# TT1-1-Top.net
KiCad netlist of a schematic drawn in Altium Designer
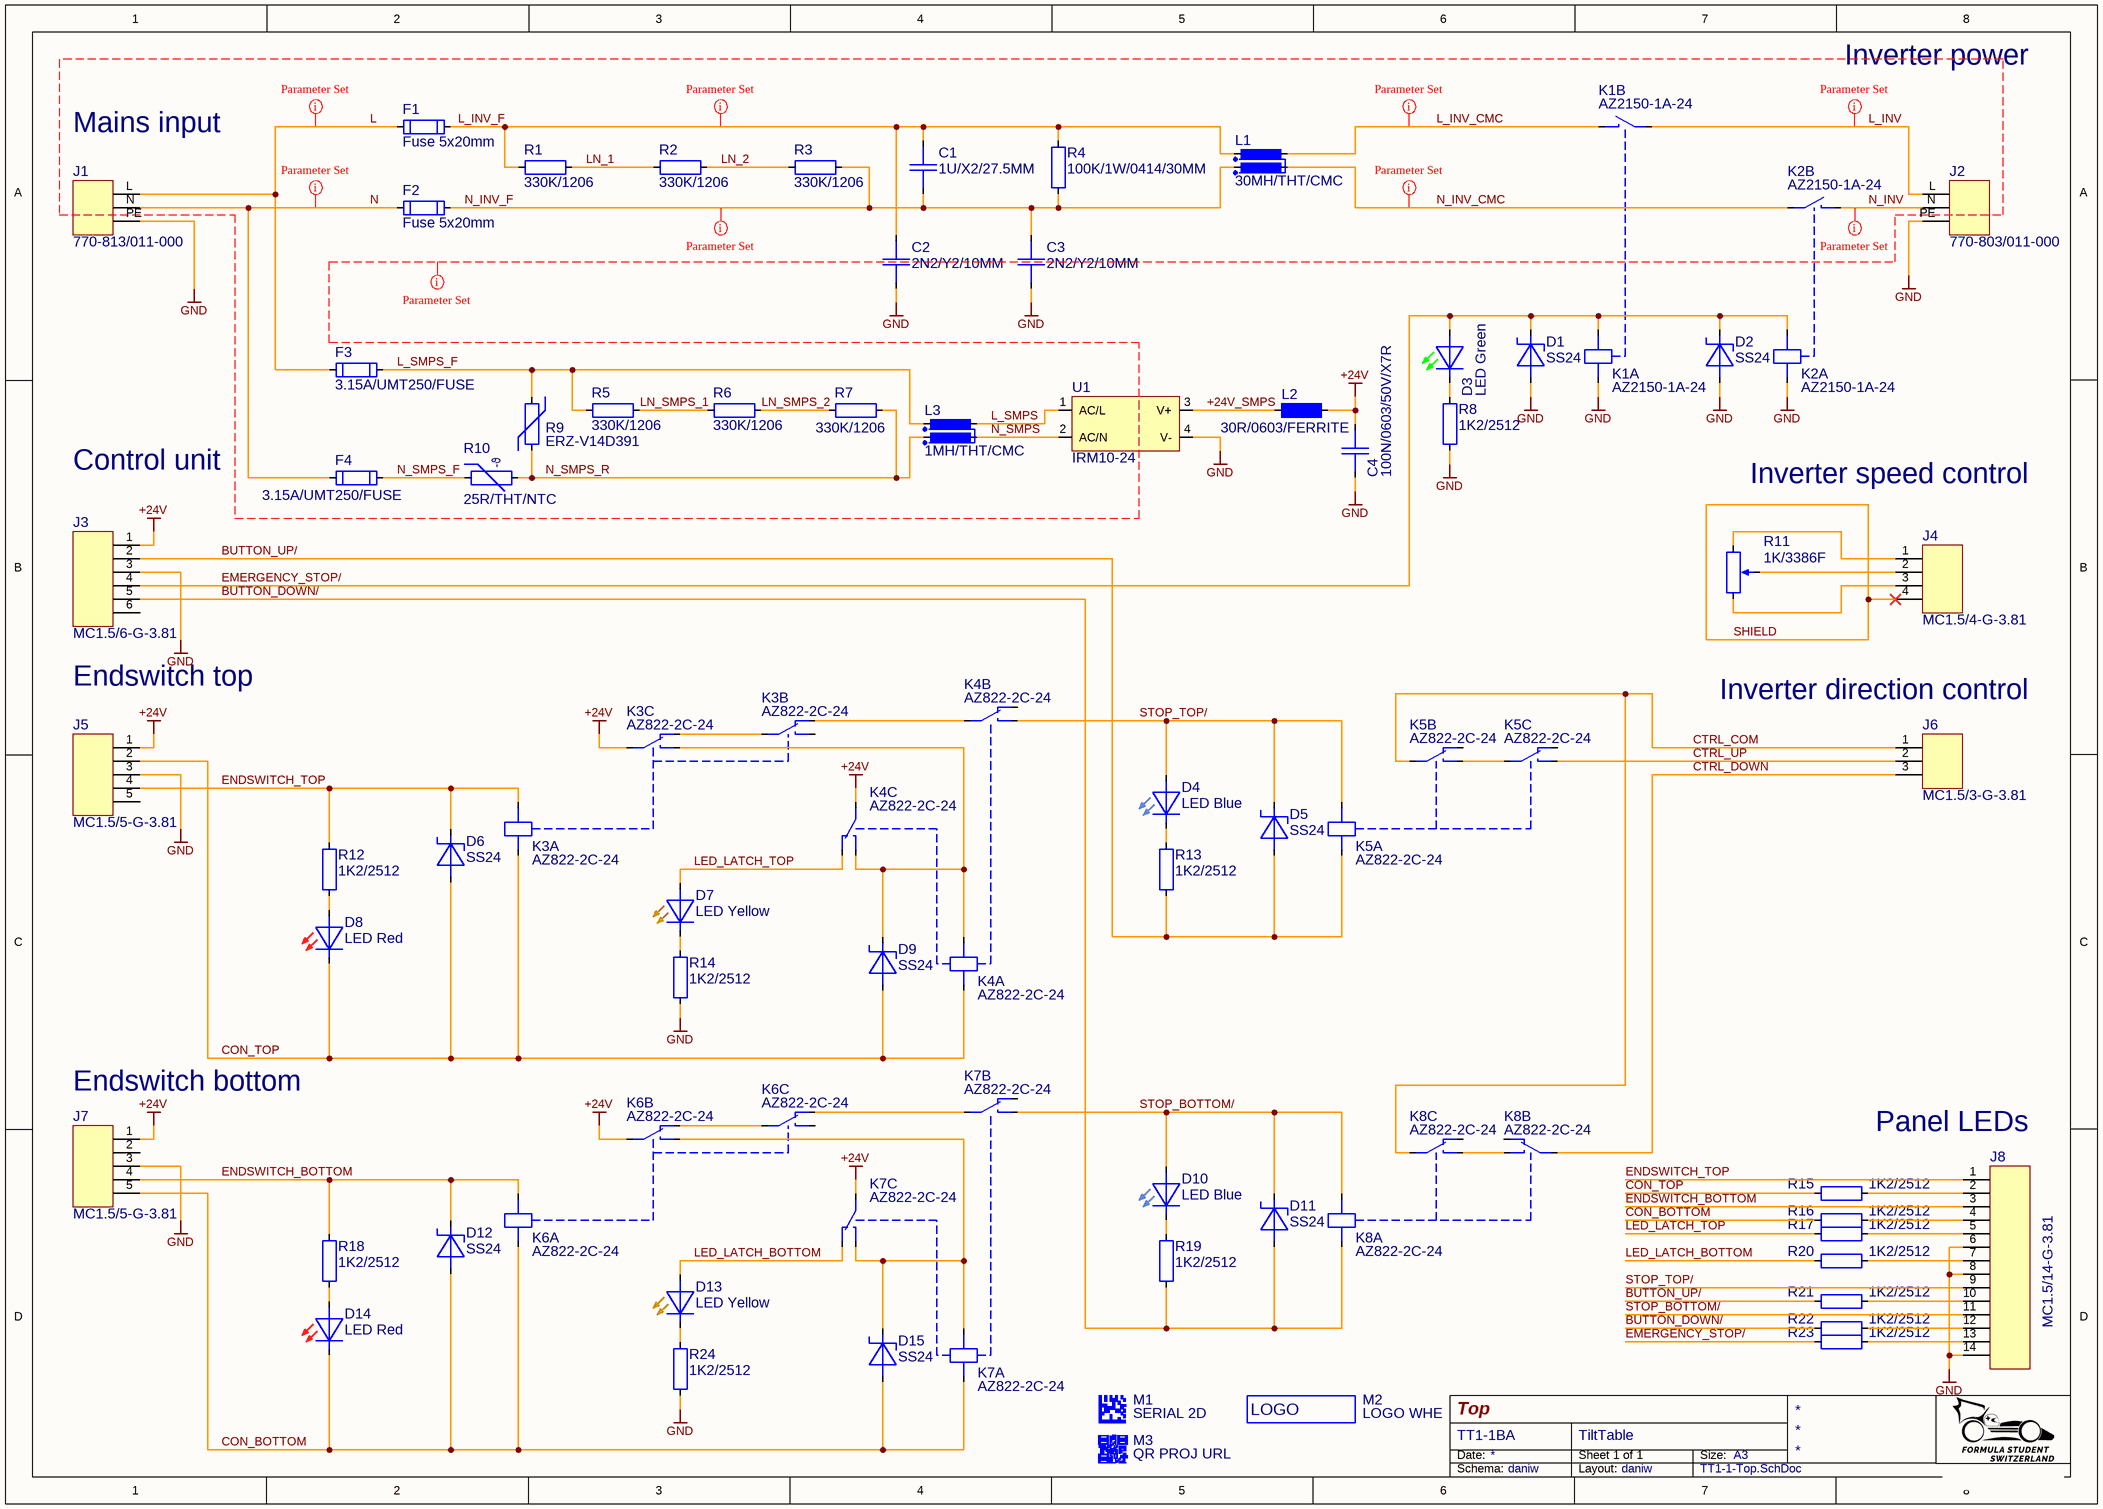
[diagram p0: TT1-1-Top.SchDoc]

(export (version "E")
  (design (tool "Eeschema 10.0.6"))
  (components
    (comp (ref "C1")
      (value "1U/X2/27.5MM")
      (footprint "CAP2750P315X110X190-BL")
      (description "CAP THT 31.5X11X19 1uF 305V X2")
      (fields (field (name "MANUFACTURER") "GENERIC"))
      (libsource (lib "daniw_altium_lib") (part "C"))
    )
    (comp (ref "C2")
      (value "2N2/Y2/10MM")
      (footprint "CAP1000P130X40X90-BL")
      (description "CAP THT 13X4X9 2.2nF 300V Y2")
      (fields (field (name "MANUFACTURER") "GENERIC"))
      (libsource (lib "daniw_altium_lib") (part "C"))
    )
    (comp (ref "C3")
      (value "2N2/Y2/10MM")
      (footprint "CAP1000P130X40X90-BL")
      (description "CAP THT 13X4X9 2.2nF 300V Y2")
      (fields (field (name "MANUFACTURER") "GENERIC"))
      (libsource (lib "daniw_altium_lib") (part "C"))
    )
    (comp (ref "C4")
      (value "100N/0603/50V/X7R")
      (footprint "CAP0603_X7R")
      (description "CAP SM 0603 100nF 50V X7R")
      (fields (field (name "MANUFACTURER") "GENERIC"))
      (libsource (lib "daniw_altium_lib") (part "C"))
    )
    (comp (ref "D1")
      (value "SS24")
      (footprint "DIOM5226X230")
      (description "Si Shottky Diode 2A DO-214AC")
      (fields (field (name "MANUFACTURER") "MSKSEMI"))
      (libsource (lib "daniw_altium_lib") (part "D_Schottky"))
    )
    (comp (ref "D2")
      (value "SS24")
      (footprint "DIOM5226X230")
      (description "Si Shottky Diode 2A DO-214AC")
      (fields (field (name "MANUFACTURER") "MSKSEMI"))
      (libsource (lib "daniw_altium_lib") (part "D_Schottky"))
    )
    (comp (ref "D3")
      (value "LED Green")
      (footprint "LED0603_GREEN")
      (description "Generic LED Green 0603")
      (fields (field (name "PART NUMBER") "LED Green 0603") (field (name "MANUFACTURER") "GENERIC"))
      (libsource (lib "daniw_altium_lib") (part "LED_GREEN"))
    )
    (comp (ref "D4")
      (value "LED Blue")
      (footprint "LED0603_BLUE")
      (description "Generic LED Blue 0603")
      (fields (field (name "PART NUMBER") "LED Blue 0603") (field (name "MANUFACTURER") "GENERIC"))
      (libsource (lib "daniw_altium_lib") (part "LED_BLUE"))
    )
    (comp (ref "D5")
      (value "SS24")
      (footprint "DIOM5226X230")
      (description "Si Shottky Diode 2A DO-214AC")
      (fields (field (name "MANUFACTURER") "MSKSEMI"))
      (libsource (lib "daniw_altium_lib") (part "D_Schottky"))
    )
    (comp (ref "D6")
      (value "SS24")
      (footprint "DIOM5226X230")
      (description "Si Shottky Diode 2A DO-214AC")
      (fields (field (name "MANUFACTURER") "MSKSEMI"))
      (libsource (lib "daniw_altium_lib") (part "D_Schottky"))
    )
    (comp (ref "D7")
      (value "LED Yellow")
      (footprint "LED0603_YELLOW")
      (description "Generic LED Yellow 0603")
      (fields (field (name "PART NUMBER") "LED Yellow 0603") (field (name "MANUFACTURER") "GENERIC"))
      (libsource (lib "daniw_altium_lib") (part "LED_YELLOW"))
    )
    (comp (ref "D8")
      (value "LED Red")
      (footprint "LED0603_RED")
      (description "Generic LED Red 0603")
      (fields (field (name "PART NUMBER") "LED Red 0603") (field (name "MANUFACTURER") "GENERIC"))
      (libsource (lib "daniw_altium_lib") (part "LED_RED"))
    )
    (comp (ref "D9")
      (value "SS24")
      (footprint "DIOM5226X230")
      (description "Si Shottky Diode 2A DO-214AC")
      (fields (field (name "MANUFACTURER") "MSKSEMI"))
      (libsource (lib "daniw_altium_lib") (part "D_Schottky"))
    )
    (comp (ref "D10")
      (value "LED Blue")
      (footprint "LED0603_BLUE")
      (description "Generic LED Blue 0603")
      (fields (field (name "PART NUMBER") "LED Blue 0603") (field (name "MANUFACTURER") "GENERIC"))
      (libsource (lib "daniw_altium_lib") (part "LED_BLUE"))
    )
    (comp (ref "D11")
      (value "SS24")
      (footprint "DIOM5226X230")
      (description "Si Shottky Diode 2A DO-214AC")
      (fields (field (name "MANUFACTURER") "MSKSEMI"))
      (libsource (lib "daniw_altium_lib") (part "D_Schottky"))
    )
    (comp (ref "D12")
      (value "SS24")
      (footprint "DIOM5226X230")
      (description "Si Shottky Diode 2A DO-214AC")
      (fields (field (name "MANUFACTURER") "MSKSEMI"))
      (libsource (lib "daniw_altium_lib") (part "D_Schottky"))
    )
    (comp (ref "D13")
      (value "LED Yellow")
      (footprint "LED0603_YELLOW")
      (description "Generic LED Yellow 0603")
      (fields (field (name "PART NUMBER") "LED Yellow 0603") (field (name "MANUFACTURER") "GENERIC"))
      (libsource (lib "daniw_altium_lib") (part "LED_YELLOW"))
    )
    (comp (ref "D14")
      (value "LED Red")
      (footprint "LED0603_RED")
      (description "Generic LED Red 0603")
      (fields (field (name "PART NUMBER") "LED Red 0603") (field (name "MANUFACTURER") "GENERIC"))
      (libsource (lib "daniw_altium_lib") (part "LED_RED"))
    )
    (comp (ref "D15")
      (value "SS24")
      (footprint "DIOM5226X230")
      (description "Si Shottky Diode 2A DO-214AC")
      (fields (field (name "MANUFACTURER") "MSKSEMI"))
      (libsource (lib "daniw_altium_lib") (part "D_Schottky"))
    )
    (comp (ref "F1")
      (value "Fuse 5x20mm")
      (footprint "OGN_THR")
      (description "open fuse holder, 5 x 20 mm, THR, IEC 60335-1")
      (fields (field (name "PART NUMBER") "Fuse/5x20mm/OGN") (field (name "MANUFACTURER") "Schurter"))
      (libsource (lib "daniw_altium_lib") (part "Fuse"))
    )
    (comp (ref "F2")
      (value "Fuse 5x20mm")
      (footprint "OGN_THR")
      (description "open fuse holder, 5 x 20 mm, THR, IEC 60335-1")
      (fields (field (name "PART NUMBER") "Fuse/5x20mm/OGN") (field (name "MANUFACTURER") "Schurter"))
      (libsource (lib "daniw_altium_lib") (part "Fuse"))
    )
    (comp (ref "F3")
      (value "3.15A/UMT250/FUSE")
      (footprint "UMT250")
      (description "Fuse 250VAC 3.15A UMT250")
      (fields (field (name "MANUFACTURER") "Schurter"))
      (libsource (lib "daniw_altium_lib") (part "Fuse"))
    )
    (comp (ref "F4")
      (value "3.15A/UMT250/FUSE")
      (footprint "UMT250")
      (description "Fuse 250VAC 3.15A UMT250")
      (fields (field (name "MANUFACTURER") "Schurter"))
      (libsource (lib "daniw_altium_lib") (part "Fuse"))
    )
    (comp (ref "J1")
      (value "770-813/011-000")
      (footprint "770-813/011-000")
      (description "Wago 770-813/011-000")
      (fields (field (name "MANUFACTURER") "Wago"))
      (libsource (lib "") (part "CON3_MAINS_1"))
    )
    (comp (ref "J2")
      (value "770-803/011-000")
      (footprint "770-803/011-000")
      (description "Wago 770-803/011-000")
      (fields (field (name "MANUFACTURER") "Wago"))
      (libsource (lib "daniw_altium_lib") (part "CON3_MAINS"))
    )
    (comp (ref "J3")
      (value "MC1.5/6-G-3.81")
      (footprint "MC1.5/6-G-3.81")
      (description "Phoenix contact MC 1,5/ 6-G-3,81")
      (fields (field (name "MANUFACTURER") "Phoenix"))
      (libsource (lib "daniw_altium_lib") (part "CON6"))
    )
    (comp (ref "J4")
      (value "MC1.5/4-G-3.81")
      (footprint "MC1.5/4-G-3.81")
      (description "Phoenix contact MC 1,5/ 4-G-3,81")
      (fields (field (name "MANUFACTURER") "Phoenix"))
      (libsource (lib "daniw_altium_lib") (part "CON4"))
    )
    (comp (ref "J5")
      (value "MC1.5/5-G-3.81")
      (footprint "MC1.5/5-G-3.81")
      (description "Phoenix contact MC 1,5/ 5-G-3,81")
      (fields (field (name "MANUFACTURER") "Phoenix"))
      (libsource (lib "daniw_altium_lib") (part "CON5"))
    )
    (comp (ref "J6")
      (value "MC1.5/3-G-3.81")
      (footprint "MC1.5/3-G-3.81")
      (description "Phoenix contact MC 1,5/ 3-G-3,81")
      (fields (field (name "MANUFACTURER") "Phoenix"))
      (libsource (lib "daniw_altium_lib") (part "CON3"))
    )
    (comp (ref "J7")
      (value "MC1.5/5-G-3.81")
      (footprint "MC1.5/5-G-3.81")
      (description "Phoenix contact MC 1,5/ 5-G-3,81")
      (fields (field (name "MANUFACTURER") "Phoenix"))
      (libsource (lib "daniw_altium_lib") (part "CON5"))
    )
    (comp (ref "J8")
      (value "MC1.5/14-G-3.81")
      (footprint "MC1.5/14-G-3.81")
      (description "Phoenix contact MC 1,5/ 14-G-3,81")
      (fields (field (name "MANUFACTURER") "Phoenix"))
      (libsource (lib "daniw_altium_lib") (part "CON14"))
    )
    (comp (ref "K1")
      (value "AZ2150-1A-24")
      (footprint "AZ2150-SPST-NO")
      (description "Miniature Power Relay, SPST-NO, 24V Coil, 40A 30VDC 300VAC")
      (fields (field (name "MANUFACTURER") "Zettler"))
      (libsource (lib "daniw_altium_lib") (part "REL_SPST_NO"))
    )
    (comp (ref "K2")
      (value "AZ2150-1A-24")
      (footprint "AZ2150-SPST-NO")
      (description "Miniature Power Relay, SPST-NO, 24V Coil, 40A 30VDC 300VAC")
      (fields (field (name "MANUFACTURER") "Zettler"))
      (libsource (lib "daniw_altium_lib") (part "REL_SPST_NO"))
    )
    (comp (ref "K3")
      (value "AZ822-2C-24")
      (footprint "AZ822")
      (description "Subminiature DIP Relay, DPDT, 24V 98mW Coil, 2A 220VDC 250VAC")
      (fields (field (name "MANUFACTURER") "Zettler"))
      (libsource (lib "daniw_altium_lib") (part "REL_DPDT"))
    )
    (comp (ref "K4")
      (value "AZ822-2C-24")
      (footprint "AZ822")
      (description "Subminiature DIP Relay, DPDT, 24V 98mW Coil, 2A 220VDC 250VAC")
      (fields (field (name "MANUFACTURER") "Zettler"))
      (libsource (lib "daniw_altium_lib") (part "REL_DPDT"))
    )
    (comp (ref "K5")
      (value "AZ822-2C-24")
      (footprint "AZ822")
      (description "Subminiature DIP Relay, DPDT, 24V 98mW Coil, 2A 220VDC 250VAC")
      (fields (field (name "MANUFACTURER") "Zettler"))
      (libsource (lib "daniw_altium_lib") (part "REL_DPDT"))
    )
    (comp (ref "K6")
      (value "AZ822-2C-24")
      (footprint "AZ822")
      (description "Subminiature DIP Relay, DPDT, 24V 98mW Coil, 2A 220VDC 250VAC")
      (fields (field (name "MANUFACTURER") "Zettler"))
      (libsource (lib "daniw_altium_lib") (part "REL_DPDT"))
    )
    (comp (ref "K7")
      (value "AZ822-2C-24")
      (footprint "AZ822")
      (description "Subminiature DIP Relay, DPDT, 24V 98mW Coil, 2A 220VDC 250VAC")
      (fields (field (name "MANUFACTURER") "Zettler"))
      (libsource (lib "daniw_altium_lib") (part "REL_DPDT"))
    )
    (comp (ref "K8")
      (value "AZ822-2C-24")
      (footprint "AZ822")
      (description "Subminiature DIP Relay, DPDT, 24V 98mW Coil, 2A 220VDC 250VAC")
      (fields (field (name "MANUFACTURER") "Zettler"))
      (libsource (lib "daniw_altium_lib") (part "REL_DPDT"))
    )
    (comp (ref "L1")
      (value "30MH/THT/CMC")
      (footprint "CMC-WE-CMBNC-XL-7448050530")
      (description "CMC 30mH 5A Würth CMBNC 7448050530")
      (fields (field (name "MANUFACTURER") "Würth"))
      (libsource (lib "daniw_altium_lib") (part "L_CMC_2"))
    )
    (comp (ref "L2")
      (value "30R/0603/FERRITE")
      (footprint "FB0603")
      (description "30R@100MHz 5A 0603 Ferrite")
      (fields (field (name "MANUFACTURER") "GENERIC"))
      (libsource (lib "daniw_altium_lib") (part "Ferrite"))
    )
    (comp (ref "L3")
      (value "1MH/THT/CMC")
      (footprint "DFKH-CASE-50-2")
      (description "CMC 1mH 2A THT Schurter DFKH-14-0003")
      (fields (field (name "MANUFACTURER") "SCHURTER"))
      (libsource (lib "daniw_altium_lib") (part "L_CMC_2"))
    )
    (comp (ref "M1")
      (value "SERIAL 2D")
      (footprint "SERIAL-2D-10MM")
      (description "2D Serial number placeholder, Dotmatrix or QR, size: 10mm")
      (fields (field (name "PART NUMBER") "SERIAL 2D 10MM") (field (name "MANUFACTURER") "NONE"))
      (libsource (lib "daniw_altium_lib") (part "SERIAL-2D"))
    )
    (comp (ref "M2")
      (value "LOGO WHE")
      (footprint "LOGO-WHE-10MM")
      (description "WHE logo, size 10mm")
      (fields (field (name "PART NUMBER") "LOGO WHE 10MM") (field (name "MANUFACTURER") "NONE"))
      (libsource (lib "daniw_altium_lib") (part "LOGO"))
    )
    (comp (ref "M3")
      (value "QR PROJ URL")
      (footprint "QR-PROJECT-URL-10MM")
      (description "QR Code, Project URL, 10mm")
      (fields (field (name "PART NUMBER") "QR PROJ URL 10MM") (field (name "MANUFACTURER") "NONE"))
      (libsource (lib "daniw_altium_lib") (part "QR-PROJ-URL"))
    )
    (comp (ref "R1")
      (value "330K/1206")
      (footprint "R1206-0.80-WW")
      (description "RES SM 1206 330K")
      (fields (field (name "MANUFACTURER") "GENERIC"))
      (libsource (lib "daniw_altium_lib") (part "R"))
    )
    (comp (ref "R2")
      (value "330K/1206")
      (footprint "R1206-0.80-WW")
      (description "RES SM 1206 330K")
      (fields (field (name "MANUFACTURER") "GENERIC"))
      (libsource (lib "daniw_altium_lib") (part "R"))
    )
    (comp (ref "R3")
      (value "330K/1206")
      (footprint "R1206-0.80-WW")
      (description "RES SM 1206 330K")
      (fields (field (name "MANUFACTURER") "GENERIC"))
      (libsource (lib "daniw_altium_lib") (part "R"))
    )
    (comp (ref "R4")
      (value "100K/1W/0414/30MM")
      (footprint "RESAD3000W80L1200D400B")
      (description "RES TH 1W 0414 30MM 100K")
      (fields (field (name "MANUFACTURER") "GENERIC"))
      (libsource (lib "daniw_altium_lib") (part "R"))
    )
    (comp (ref "R5")
      (value "330K/1206")
      (footprint "R1206-0.80-WW")
      (description "RES SM 1206 330K")
      (fields (field (name "MANUFACTURER") "GENERIC"))
      (libsource (lib "daniw_altium_lib") (part "R"))
    )
    (comp (ref "R6")
      (value "330K/1206")
      (footprint "R1206-0.80-WW")
      (description "RES SM 1206 330K")
      (fields (field (name "MANUFACTURER") "GENERIC"))
      (libsource (lib "daniw_altium_lib") (part "R"))
    )
    (comp (ref "R7")
      (value "330K/1206")
      (footprint "R1206-0.80-WW")
      (description "RES SM 1206 330K")
      (fields (field (name "MANUFACTURER") "GENERIC"))
      (libsource (lib "daniw_altium_lib") (part "R"))
    )
    (comp (ref "R8")
      (value "1K2/2512")
      (footprint "R2512-0.65-WW")
      (description "RES SM 2512 1K2")
      (fields (field (name "MANUFACTURER") "GENERIC"))
      (libsource (lib "daniw_altium_lib") (part "R"))
    )
    (comp (ref "R9")
      (value "ERZ-V14D391")
      (footprint "RESD750W80D155")
      (description "VARISTOR 391V 6kA")
      (fields (field (name "MANUFACTURER") "GENERIC"))
      (libsource (lib "daniw_altium_lib") (part "R_VAR"))
    )
    (comp (ref "R10")
      (value "25R/THT/NTC")
      (footprint "RESD500W60D115")
      (description "RES NTC THT 5 25R")
      (fields (field (name "MANUFACTURER") "GENERIC"))
      (libsource (lib "daniw_altium_lib") (part "R_NTC"))
    )
    (comp (ref "R11")
      (value "1K/3386F")
      (footprint "3386F")
      (description "RES POT 3386F 1K")
      (fields (field (name "MANUFACTURER") "Bourns"))
      (libsource (lib "daniw_altium_lib") (part "R_POT"))
    )
    (comp (ref "R12")
      (value "1K2/2512")
      (footprint "R2512-0.65-WW")
      (description "RES SM 2512 1K2")
      (fields (field (name "MANUFACTURER") "GENERIC"))
      (libsource (lib "daniw_altium_lib") (part "R"))
    )
    (comp (ref "R13")
      (value "1K2/2512")
      (footprint "R2512-0.65-WW")
      (description "RES SM 2512 1K2")
      (fields (field (name "MANUFACTURER") "GENERIC"))
      (libsource (lib "daniw_altium_lib") (part "R"))
    )
    (comp (ref "R14")
      (value "1K2/2512")
      (footprint "R2512-0.65-WW")
      (description "RES SM 2512 1K2")
      (fields (field (name "MANUFACTURER") "GENERIC"))
      (libsource (lib "daniw_altium_lib") (part "R"))
    )
    (comp (ref "R15")
      (value "1K2/2512")
      (footprint "R2512-0.65-WW")
      (description "RES SM 2512 1K2")
      (fields (field (name "MANUFACTURER") "GENERIC"))
      (libsource (lib "daniw_altium_lib") (part "R"))
    )
    (comp (ref "R16")
      (value "1K2/2512")
      (footprint "R2512-0.65-WW")
      (description "RES SM 2512 1K2")
      (fields (field (name "MANUFACTURER") "GENERIC"))
      (libsource (lib "daniw_altium_lib") (part "R"))
    )
    (comp (ref "R17")
      (value "1K2/2512")
      (footprint "R2512-0.65-WW")
      (description "RES SM 2512 1K2")
      (fields (field (name "MANUFACTURER") "GENERIC"))
      (libsource (lib "daniw_altium_lib") (part "R"))
    )
    (comp (ref "R18")
      (value "1K2/2512")
      (footprint "R2512-0.65-WW")
      (description "RES SM 2512 1K2")
      (fields (field (name "MANUFACTURER") "GENERIC"))
      (libsource (lib "daniw_altium_lib") (part "R"))
    )
    (comp (ref "R19")
      (value "1K2/2512")
      (footprint "R2512-0.65-WW")
      (description "RES SM 2512 1K2")
      (fields (field (name "MANUFACTURER") "GENERIC"))
      (libsource (lib "daniw_altium_lib") (part "R"))
    )
    (comp (ref "R20")
      (value "1K2/2512")
      (footprint "R2512-0.65-WW")
      (description "RES SM 2512 1K2")
      (fields (field (name "MANUFACTURER") "GENERIC"))
      (libsource (lib "daniw_altium_lib") (part "R"))
    )
    (comp (ref "R21")
      (value "1K2/2512")
      (footprint "R2512-0.65-WW")
      (description "RES SM 2512 1K2")
      (fields (field (name "MANUFACTURER") "GENERIC"))
      (libsource (lib "daniw_altium_lib") (part "R"))
    )
    (comp (ref "R22")
      (value "1K2/2512")
      (footprint "R2512-0.65-WW")
      (description "RES SM 2512 1K2")
      (fields (field (name "MANUFACTURER") "GENERIC"))
      (libsource (lib "daniw_altium_lib") (part "R"))
    )
    (comp (ref "R23")
      (value "1K2/2512")
      (footprint "R2512-0.65-WW")
      (description "RES SM 2512 1K2")
      (fields (field (name "MANUFACTURER") "GENERIC"))
      (libsource (lib "daniw_altium_lib") (part "R"))
    )
    (comp (ref "R24")
      (value "1K2/2512")
      (footprint "R2512-0.65-WW")
      (description "RES SM 2512 1K2")
      (fields (field (name "MANUFACTURER") "GENERIC"))
      (libsource (lib "daniw_altium_lib") (part "R"))
    )
    (comp (ref "U1")
      (value "IRM10-24")
      (footprint "IRM10")
      (description "10W AC-DC PCB-Mount Green Power Module, 24V")
      (libsource (lib "daniw_altium_lib") (part "IRM30"))
    )
  )
  (nets
    (net (code "1") (name "+24V") (class "Default")
      (node (ref "C4") (pin "1") (pinfunction "1_1") (pintype "passive"))
      (node (ref "J3") (pin "1") (pintype "passive"))
      (node (ref "J5") (pin "1") (pintype "passive"))
      (node (ref "J7") (pin "1") (pintype "passive"))
      (node (ref "K3") (pin "6") (pinfunction "COM2_6") (pintype "passive"))
      (node (ref "K4") (pin "6") (pinfunction "COM2_6") (pintype "passive"))
      (node (ref "K6") (pin "3") (pinfunction "COM1_3") (pintype "passive"))
      (node (ref "K7") (pin "6") (pinfunction "COM2_6") (pintype "passive"))
      (node (ref "L2") (pin "2") (pinfunction "2_2") (pintype "passive"))
    )
    (net (code "2") (name "/+24V_SMPS") (class "Default")
      (node (ref "L2") (pin "1") (pinfunction "1_1") (pintype "passive"))
      (node (ref "U1") (pin "3") (pinfunction "V+_3") (pintype "passive"))
    )
    (net (code "3") (name "/BUTTON_DOWN{slash}") (class "Default")
      (node (ref "D11") (pin "2") (pinfunction "2_2") (pintype "passive"))
      (node (ref "J3") (pin "5") (pintype "passive"))
      (node (ref "K8") (pin "2") (pinfunction "2_2") (pintype "passive"))
      (node (ref "R19") (pin "2") (pinfunction "2_2") (pintype "passive"))
      (node (ref "R22") (pin "1") (pinfunction "1_1") (pintype "passive"))
    )
    (net (code "4") (name "/BUTTON_UP{slash}") (class "Default")
      (node (ref "D5") (pin "2") (pinfunction "2_2") (pintype "passive"))
      (node (ref "J3") (pin "2") (pintype "passive"))
      (node (ref "K5") (pin "1") (pinfunction "1_1") (pintype "passive"))
      (node (ref "R13") (pin "2") (pinfunction "2_2") (pintype "passive"))
      (node (ref "R21") (pin "1") (pinfunction "1_1") (pintype "passive"))
    )
    (net (code "5") (name "/CON_BOTTOM") (class "Default")
      (node (ref "D12") (pin "2") (pinfunction "2_2") (pintype "passive"))
      (node (ref "D14") (pin "1") (pinfunction "1_1") (pintype "passive"))
      (node (ref "D15") (pin "2") (pinfunction "2_2") (pintype "passive"))
      (node (ref "J7") (pin "5") (pintype "passive"))
      (node (ref "K6") (pin "2") (pinfunction "2_2") (pintype "passive"))
      (node (ref "K7") (pin "2") (pinfunction "2_2") (pintype "passive"))
      (node (ref "R16") (pin "1") (pinfunction "1_1") (pintype "passive"))
    )
    (net (code "6") (name "/CON_TOP") (class "Default")
      (node (ref "D6") (pin "2") (pinfunction "2_2") (pintype "passive"))
      (node (ref "D8") (pin "1") (pinfunction "1_1") (pintype "passive"))
      (node (ref "D9") (pin "2") (pinfunction "2_2") (pintype "passive"))
      (node (ref "J5") (pin "2") (pintype "passive"))
      (node (ref "K3") (pin "2") (pinfunction "2_2") (pintype "passive"))
      (node (ref "K4") (pin "2") (pinfunction "2_2") (pintype "passive"))
      (node (ref "R15") (pin "1") (pinfunction "1_1") (pintype "passive"))
    )
    (net (code "7") (name "/CTRL_COM") (class "Default")
      (node (ref "J6") (pin "1") (pintype "passive"))
      (node (ref "K5") (pin "3") (pinfunction "COM1_3") (pintype "passive"))
      (node (ref "K8") (pin "6") (pinfunction "COM2_6") (pintype "passive"))
    )
    (net (code "8") (name "/CTRL_DOWN") (class "Default")
      (node (ref "J6") (pin "3") (pintype "passive"))
      (node (ref "K8") (pin "3") (pinfunction "COM1_3") (pintype "passive"))
    )
    (net (code "9") (name "/CTRL_UP") (class "Default")
      (node (ref "J6") (pin "2") (pintype "passive"))
      (node (ref "K5") (pin "8") (pinfunction "NO2_8") (pintype "passive"))
    )
    (net (code "10") (name "/EMERGENCY_STOP{slash}") (class "Default")
      (node (ref "D1") (pin "1") (pinfunction "1_1") (pintype "passive"))
      (node (ref "D2") (pin "1") (pinfunction "1_1") (pintype "passive"))
      (node (ref "D3") (pin "2") (pinfunction "2_2") (pintype "passive"))
      (node (ref "J3") (pin "4") (pintype "passive"))
      (node (ref "K1") (pin "1") (pinfunction "1_1") (pintype "passive"))
      (node (ref "K2") (pin "1") (pinfunction "1_1") (pintype "passive"))
      (node (ref "R23") (pin "1") (pinfunction "1_1") (pintype "passive"))
    )
    (net (code "11") (name "/ENDSWITCH_BOTTOM") (class "Default")
      (node (ref "D12") (pin "1") (pinfunction "1_1") (pintype "passive"))
      (node (ref "J7") (pin "4") (pintype "passive"))
      (node (ref "J8") (pin "3") (pintype "passive"))
      (node (ref "K6") (pin "1") (pinfunction "1_1") (pintype "passive"))
      (node (ref "R18") (pin "1") (pinfunction "1_1") (pintype "passive"))
    )
    (net (code "12") (name "/ENDSWITCH_TOP") (class "Default")
      (node (ref "D6") (pin "1") (pinfunction "1_1") (pintype "passive"))
      (node (ref "J5") (pin "4") (pintype "passive"))
      (node (ref "J8") (pin "1") (pintype "passive"))
      (node (ref "K3") (pin "1") (pinfunction "1_1") (pintype "passive"))
      (node (ref "R12") (pin "1") (pinfunction "1_1") (pintype "passive"))
    )
    (net (code "13") (name "/L") (class "Default")
      (node (ref "F1") (pin "1") (pinfunction "1_1") (pintype "passive"))
      (node (ref "F3") (pin "1") (pinfunction "1_1") (pintype "passive"))
      (node (ref "J1") (pin "L") (pintype "passive"))
    )
    (net (code "14") (name "/LED_LATCH_BOTTOM") (class "Default")
      (node (ref "D13") (pin "2") (pinfunction "2_2") (pintype "passive"))
      (node (ref "K7") (pin "7") (pinfunction "NC2_7") (pintype "passive"))
      (node (ref "R20") (pin "1") (pinfunction "1_1") (pintype "passive"))
    )
    (net (code "15") (name "/LED_LATCH_TOP") (class "Default")
      (node (ref "D7") (pin "2") (pinfunction "2_2") (pintype "passive"))
      (node (ref "K4") (pin "7") (pinfunction "NC2_7") (pintype "passive"))
      (node (ref "R17") (pin "1") (pinfunction "1_1") (pintype "passive"))
    )
    (net (code "16") (name "/LN_1") (class "Default")
      (node (ref "R1") (pin "2") (pinfunction "2_2") (pintype "passive"))
      (node (ref "R2") (pin "1") (pinfunction "1_1") (pintype "passive"))
    )
    (net (code "17") (name "/LN_2") (class "Default")
      (node (ref "R2") (pin "2") (pinfunction "2_2") (pintype "passive"))
      (node (ref "R3") (pin "1") (pinfunction "1_1") (pintype "passive"))
    )
    (net (code "18") (name "/LN_SMPS_1") (class "Default")
      (node (ref "R5") (pin "2") (pinfunction "2_2") (pintype "passive"))
      (node (ref "R6") (pin "2") (pinfunction "2_2") (pintype "passive"))
    )
    (net (code "19") (name "/LN_SMPS_2") (class "Default")
      (node (ref "R6") (pin "1") (pinfunction "1_1") (pintype "passive"))
      (node (ref "R7") (pin "1") (pinfunction "1_1") (pintype "passive"))
    )
    (net (code "20") (name "/L_INV") (class "Default")
      (node (ref "J2") (pin "L") (pintype "passive"))
      (node (ref "K1") (pin "3") (pinfunction "COM1_3") (pintype "passive"))
    )
    (net (code "21") (name "/L_INV_CMC") (class "Default")
      (node (ref "K1") (pin "4") (pinfunction "NO1_4") (pintype "passive"))
      (node (ref "L1") (pin "3") (pinfunction "3_3") (pintype "passive"))
    )
    (net (code "22") (name "/L_INV_F") (class "Default")
      (node (ref "C1") (pin "1") (pinfunction "1_1") (pintype "passive"))
      (node (ref "C2") (pin "1") (pinfunction "1_1") (pintype "passive"))
      (node (ref "F1") (pin "2") (pinfunction "2_2") (pintype "passive"))
      (node (ref "L1") (pin "1") (pinfunction "1_1") (pintype "passive"))
      (node (ref "R1") (pin "1") (pinfunction "1_1") (pintype "passive"))
      (node (ref "R4") (pin "1") (pinfunction "1_1") (pintype "passive"))
    )
    (net (code "23") (name "/L_SMPS") (class "Default")
      (node (ref "L3") (pin "3") (pinfunction "3_3") (pintype "passive"))
      (node (ref "U1") (pin "1") (pinfunction "AC/L_1") (pintype "passive"))
    )
    (net (code "24") (name "/L_SMPS_F") (class "Default")
      (node (ref "F3") (pin "2") (pinfunction "2_2") (pintype "passive"))
      (node (ref "L3") (pin "1") (pinfunction "1_1") (pintype "passive"))
      (node (ref "R5") (pin "1") (pinfunction "1_1") (pintype "passive"))
      (node (ref "R9") (pin "1") (pinfunction "1_1") (pintype "passive"))
    )
    (net (code "25") (name "/N") (class "Default")
      (node (ref "F2") (pin "1") (pinfunction "1_1") (pintype "passive"))
      (node (ref "F4") (pin "1") (pinfunction "1_1") (pintype "passive"))
      (node (ref "J1") (pin "N") (pintype "passive"))
    )
    (net (code "26") (name "/N_INV") (class "Default")
      (node (ref "J2") (pin "N") (pintype "passive"))
      (node (ref "K2") (pin "4") (pinfunction "NO1_4") (pintype "passive"))
    )
    (net (code "27") (name "/N_INV_CMC") (class "Default")
      (node (ref "K2") (pin "3") (pinfunction "COM1_3") (pintype "passive"))
      (node (ref "L1") (pin "4") (pinfunction "4_4") (pintype "passive"))
    )
    (net (code "28") (name "/N_INV_F") (class "Default")
      (node (ref "C1") (pin "2") (pinfunction "2_2") (pintype "passive"))
      (node (ref "C3") (pin "1") (pinfunction "1_1") (pintype "passive"))
      (node (ref "F2") (pin "2") (pinfunction "2_2") (pintype "passive"))
      (node (ref "L1") (pin "2") (pinfunction "2_2") (pintype "passive"))
      (node (ref "R3") (pin "2") (pinfunction "2_2") (pintype "passive"))
      (node (ref "R4") (pin "2") (pinfunction "2_2") (pintype "passive"))
    )
    (net (code "29") (name "/N_SMPS") (class "Default")
      (node (ref "L3") (pin "4") (pinfunction "4_4") (pintype "passive"))
      (node (ref "U1") (pin "2") (pinfunction "AC/N_2") (pintype "passive"))
    )
    (net (code "30") (name "/N_SMPS_F") (class "Default")
      (node (ref "F4") (pin "2") (pinfunction "2_2") (pintype "passive"))
      (node (ref "R10") (pin "1") (pinfunction "1_1") (pintype "passive"))
    )
    (net (code "31") (name "/N_SMPS_R") (class "Default")
      (node (ref "L3") (pin "2") (pinfunction "2_2") (pintype "passive"))
      (node (ref "R10") (pin "2") (pinfunction "2_2") (pintype "passive"))
      (node (ref "R7") (pin "2") (pinfunction "2_2") (pintype "passive"))
      (node (ref "R9") (pin "2") (pinfunction "2_2") (pintype "passive"))
    )
    (net (code "32") (name "/SHIELD") (class "Default")
      (node (ref "J4") (pin "4") (pintype "passive+no_connect"))
    )
    (net (code "33") (name "/STOP_BOTTOM{slash}") (class "Default")
      (node (ref "D10") (pin "2") (pinfunction "2_2") (pintype "passive"))
      (node (ref "D11") (pin "1") (pinfunction "1_1") (pintype "passive"))
      (node (ref "J8") (pin "11") (pintype "passive"))
      (node (ref "K7") (pin "5") (pinfunction "NO1_5") (pintype "passive"))
      (node (ref "K8") (pin "1") (pinfunction "1_1") (pintype "passive"))
    )
    (net (code "34") (name "/STOP_TOP{slash}") (class "Default")
      (node (ref "D4") (pin "2") (pinfunction "2_2") (pintype "passive"))
      (node (ref "D5") (pin "1") (pinfunction "1_1") (pintype "passive"))
      (node (ref "J8") (pin "9") (pintype "passive"))
      (node (ref "K4") (pin "5") (pinfunction "NO1_5") (pintype "passive"))
      (node (ref "K5") (pin "2") (pinfunction "2_2") (pintype "passive"))
    )
    (net (code "35") (name "GND") (class "Default")
      (node (ref "C2") (pin "2") (pinfunction "2_2") (pintype "passive"))
      (node (ref "C3") (pin "2") (pinfunction "2_2") (pintype "passive"))
      (node (ref "C4") (pin "2") (pinfunction "2_2") (pintype "passive"))
      (node (ref "D1") (pin "2") (pinfunction "2_2") (pintype "passive"))
      (node (ref "D2") (pin "2") (pinfunction "2_2") (pintype "passive"))
      (node (ref "J1") (pin "PE") (pintype "passive"))
      (node (ref "J2") (pin "PE") (pintype "passive"))
      (node (ref "J3") (pin "3") (pintype "passive"))
      (node (ref "J5") (pin "3") (pintype "passive"))
      (node (ref "J7") (pin "3") (pintype "passive"))
      (node (ref "J8") (pin "14") (pintype "passive"))
      (node (ref "J8") (pin "6") (pintype "passive"))
      (node (ref "J8") (pin "8") (pintype "passive"))
      (node (ref "K1") (pin "2") (pinfunction "2_2") (pintype "passive"))
      (node (ref "K2") (pin "2") (pinfunction "2_2") (pintype "passive"))
      (node (ref "R14") (pin "2") (pinfunction "2_2") (pintype "passive"))
      (node (ref "R24") (pin "2") (pinfunction "2_2") (pintype "passive"))
      (node (ref "R8") (pin "2") (pinfunction "2_2") (pintype "passive"))
      (node (ref "U1") (pin "4") (pinfunction "V-_4") (pintype "passive"))
    )
    (net (code "36") (name "Net-(D3-Pad1)") (class "Default")
      (node (ref "D3") (pin "1") (pinfunction "1_1") (pintype "passive"))
      (node (ref "R8") (pin "1") (pinfunction "1_1") (pintype "passive"))
    )
    (net (code "37") (name "Net-(D4-Pad1)") (class "Default")
      (node (ref "D4") (pin "1") (pinfunction "1_1") (pintype "passive"))
      (node (ref "R13") (pin "1") (pinfunction "1_1") (pintype "passive"))
    )
    (net (code "38") (name "Net-(D7-Pad1)") (class "Default")
      (node (ref "D7") (pin "1") (pinfunction "1_1") (pintype "passive"))
      (node (ref "R14") (pin "1") (pinfunction "1_1") (pintype "passive"))
    )
    (net (code "39") (name "Net-(D8-Pad2)") (class "Default")
      (node (ref "D8") (pin "2") (pinfunction "2_2") (pintype "passive"))
      (node (ref "R12") (pin "2") (pinfunction "2_2") (pintype "passive"))
    )
    (net (code "40") (name "Net-(D10-Pad1)") (class "Default")
      (node (ref "D10") (pin "1") (pinfunction "1_1") (pintype "passive"))
      (node (ref "R19") (pin "1") (pinfunction "1_1") (pintype "passive"))
    )
    (net (code "41") (name "Net-(D13-Pad1)") (class "Default")
      (node (ref "D13") (pin "1") (pinfunction "1_1") (pintype "passive"))
      (node (ref "R24") (pin "1") (pinfunction "1_1") (pintype "passive"))
    )
    (net (code "42") (name "Net-(D14-Pad2)") (class "Default")
      (node (ref "D14") (pin "2") (pinfunction "2_2") (pintype "passive"))
      (node (ref "R18") (pin "2") (pinfunction "2_2") (pintype "passive"))
    )
    (net (code "43") (name "Net-(J4-Pad1)") (class "Default")
      (node (ref "J4") (pin "1") (pintype "passive"))
      (node (ref "R11") (pin "2") (pinfunction "2_2") (pintype "passive"))
    )
    (net (code "44") (name "Net-(J4-Pad2)") (class "Default")
      (node (ref "J4") (pin "2") (pintype "passive"))
      (node (ref "R11") (pin "3") (pinfunction "3_3") (pintype "passive"))
    )
    (net (code "45") (name "Net-(J4-Pad3)") (class "Default")
      (node (ref "J4") (pin "3") (pintype "passive"))
      (node (ref "R11") (pin "1") (pinfunction "1_1") (pintype "passive"))
    )
    (net (code "46") (name "Net-(J8-Pad2)") (class "Default")
      (node (ref "J8") (pin "2") (pintype "passive"))
      (node (ref "R15") (pin "2") (pinfunction "2_2") (pintype "passive"))
    )
    (net (code "47") (name "Net-(J8-Pad4)") (class "Default")
      (node (ref "J8") (pin "4") (pintype "passive"))
      (node (ref "R16") (pin "2") (pinfunction "2_2") (pintype "passive"))
    )
    (net (code "48") (name "Net-(J8-Pad5)") (class "Default")
      (node (ref "J8") (pin "5") (pintype "passive"))
      (node (ref "R17") (pin "2") (pinfunction "2_2") (pintype "passive"))
    )
    (net (code "49") (name "Net-(J8-Pad7)") (class "Default")
      (node (ref "J8") (pin "7") (pintype "passive"))
      (node (ref "R20") (pin "2") (pinfunction "2_2") (pintype "passive"))
    )
    (net (code "50") (name "Net-(J8-Pad10)") (class "Default")
      (node (ref "J8") (pin "10") (pintype "passive"))
      (node (ref "R21") (pin "2") (pinfunction "2_2") (pintype "passive"))
    )
    (net (code "51") (name "Net-(J8-Pad12)") (class "Default")
      (node (ref "J8") (pin "12") (pintype "passive"))
      (node (ref "R22") (pin "2") (pinfunction "2_2") (pintype "passive"))
    )
    (net (code "52") (name "Net-(J8-Pad13)") (class "Default")
      (node (ref "J8") (pin "13") (pintype "passive"))
      (node (ref "R23") (pin "2") (pinfunction "2_2") (pintype "passive"))
    )
    (net (code "53") (name "Net-(K3B-COM1)") (class "Default")
      (node (ref "K3") (pin "3") (pinfunction "COM1_3") (pintype "passive"))
      (node (ref "K3") (pin "7") (pinfunction "NC2_7") (pintype "passive"))
    )
    (net (code "54") (name "Net-(K3B-NC1)") (class "Default")
      (node (ref "K3") (pin "4") (pinfunction "NC1_4") (pintype "passive"))
      (node (ref "K4") (pin "3") (pinfunction "COM1_3") (pintype "passive"))
    )
    (net (code "55") (name "Net-(K3C-NO2)") (class "Default")
      (node (ref "D9") (pin "1") (pinfunction "1_1") (pintype "passive"))
      (node (ref "K3") (pin "8") (pinfunction "NO2_8") (pintype "passive"))
      (node (ref "K4") (pin "1") (pinfunction "1_1") (pintype "passive"))
      (node (ref "K4") (pin "8") (pinfunction "NO2_8") (pintype "passive"))
    )
    (net (code "56") (name "Net-(K5B-NO1)") (class "Default")
      (node (ref "K5") (pin "5") (pinfunction "NO1_5") (pintype "passive"))
      (node (ref "K5") (pin "6") (pinfunction "COM2_6") (pintype "passive"))
    )
    (net (code "57") (name "Net-(K6B-NC1)") (class "Default")
      (node (ref "K6") (pin "4") (pinfunction "NC1_4") (pintype "passive"))
      (node (ref "K6") (pin "6") (pinfunction "COM2_6") (pintype "passive"))
    )
    (net (code "58") (name "Net-(K6B-NO1)") (class "Default")
      (node (ref "D15") (pin "1") (pinfunction "1_1") (pintype "passive"))
      (node (ref "K6") (pin "5") (pinfunction "NO1_5") (pintype "passive"))
      (node (ref "K7") (pin "1") (pinfunction "1_1") (pintype "passive"))
      (node (ref "K7") (pin "8") (pinfunction "NO2_8") (pintype "passive"))
    )
    (net (code "59") (name "Net-(K6C-NC2)") (class "Default")
      (node (ref "K6") (pin "7") (pinfunction "NC2_7") (pintype "passive"))
      (node (ref "K7") (pin "3") (pinfunction "COM1_3") (pintype "passive"))
    )
    (net (code "60") (name "Net-(K8B-NO1)") (class "Default")
      (node (ref "K8") (pin "5") (pinfunction "NO1_5") (pintype "passive"))
      (node (ref "K8") (pin "8") (pinfunction "NO2_8") (pintype "passive"))
    )
    (net (code "61") (name "unconnected-(J3-Pad6)") (class "Default")
      (node (ref "J3") (pin "6") (pintype "passive"))
    )
    (net (code "62") (name "unconnected-(J5-Pad5)") (class "Default")
      (node (ref "J5") (pin "5") (pintype "passive"))
    )
    (net (code "63") (name "unconnected-(J7-Pad2)") (class "Default")
      (node (ref "J7") (pin "2") (pintype "passive"))
    )
    (net (code "64") (name "unconnected-(K3B-NO1-Pad5)") (class "Default")
      (node (ref "K3") (pin "5") (pinfunction "NO1_5") (pintype "passive"))
    )
    (net (code "65") (name "unconnected-(K4B-NC1-Pad4)") (class "Default")
      (node (ref "K4") (pin "4") (pinfunction "NC1_4") (pintype "passive"))
    )
    (net (code "66") (name "unconnected-(K5B-NC1-Pad4)") (class "Default")
      (node (ref "K5") (pin "4") (pinfunction "NC1_4") (pintype "passive"))
    )
    (net (code "67") (name "unconnected-(K5C-NC2-Pad7)") (class "Default")
      (node (ref "K5") (pin "7") (pinfunction "NC2_7") (pintype "passive"))
    )
    (net (code "68") (name "unconnected-(K6C-NO2-Pad8)") (class "Default")
      (node (ref "K6") (pin "8") (pinfunction "NO2_8") (pintype "passive"))
    )
    (net (code "69") (name "unconnected-(K7B-NC1-Pad4)") (class "Default")
      (node (ref "K7") (pin "4") (pinfunction "NC1_4") (pintype "passive"))
    )
    (net (code "70") (name "unconnected-(K8B-NC1-Pad4)") (class "Default")
      (node (ref "K8") (pin "4") (pinfunction "NC1_4") (pintype "passive"))
    )
    (net (code "71") (name "unconnected-(K8C-NC2-Pad7)") (class "Default")
      (node (ref "K8") (pin "7") (pinfunction "NC2_7") (pintype "passive"))
    )
  )
)
